# scheme.net
KiCad netlist of a schematic drawn in EAGLE
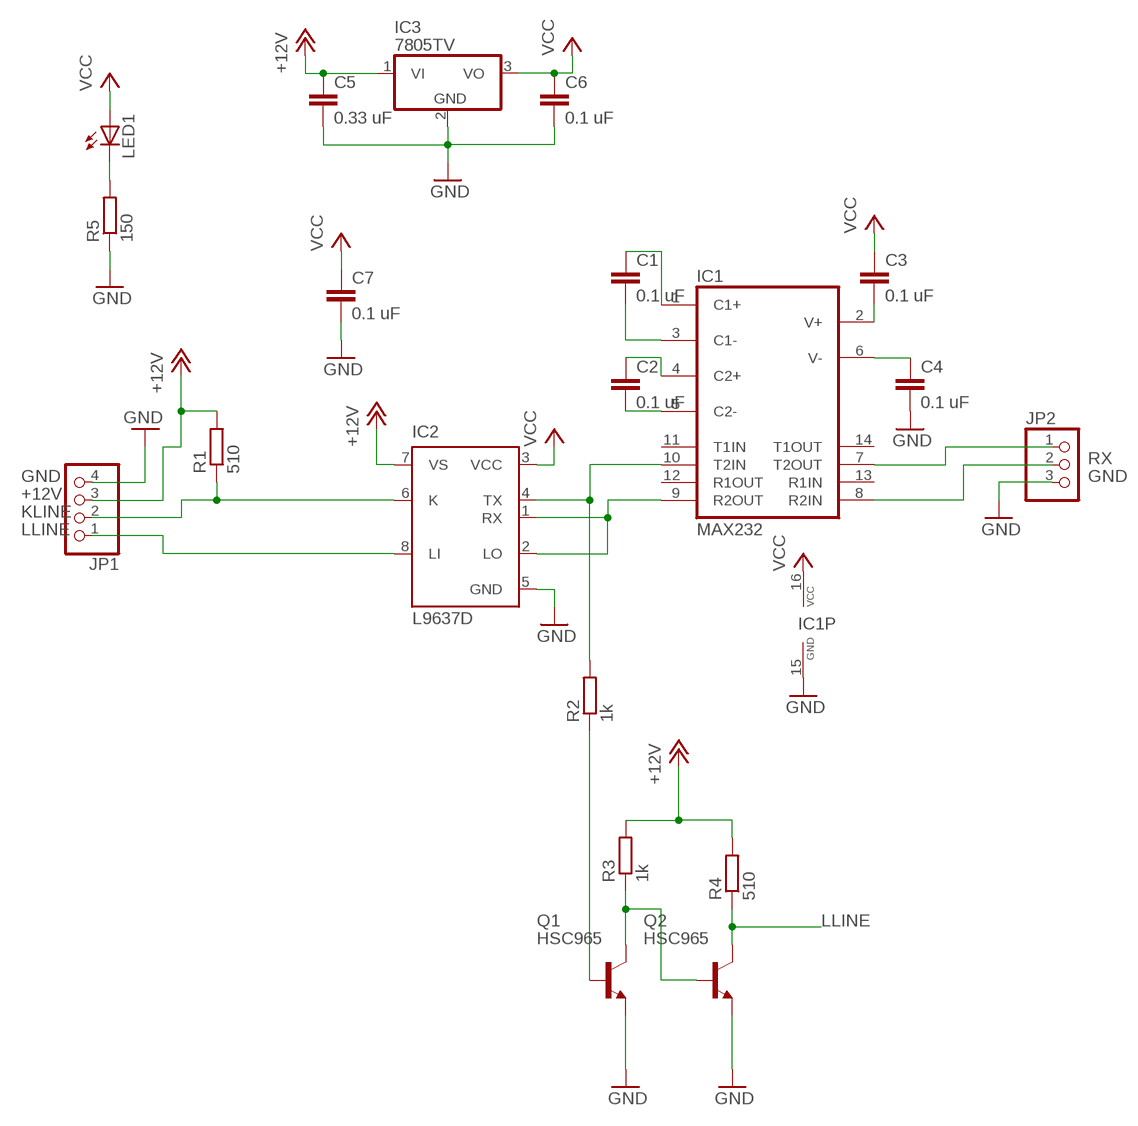
[diagram p0: schematic, sheet 1]

(export (version "E")
  (design (tool "Eeschema 10.0.6"))
  (components
    (comp (ref "C1")
      (value "0.1 uF")
      (footprint "eagle-import:C0805K")
      (libsource (lib "eagle-import") (part "C-EUC0805K"))
    )
    (comp (ref "C2")
      (value "0.1 uF")
      (footprint "eagle-import:C0805K")
      (libsource (lib "eagle-import") (part "C-EUC0805K"))
    )
    (comp (ref "C3")
      (value "0.1 uF")
      (footprint "eagle-import:C0805K")
      (libsource (lib "eagle-import") (part "C-EUC0805K"))
    )
    (comp (ref "C4")
      (value "0.1 uF")
      (footprint "eagle-import:C0805K")
      (libsource (lib "eagle-import") (part "C-EUC0805K"))
    )
    (comp (ref "C5")
      (value "0.33 uF")
      (footprint "eagle-import:C0805K")
      (libsource (lib "eagle-import") (part "C-EUC0805K"))
    )
    (comp (ref "C6")
      (value "0.1 uF")
      (footprint "eagle-import:C0805K")
      (libsource (lib "eagle-import") (part "C-EUC0805K"))
    )
    (comp (ref "C7")
      (value "0.1 uF")
      (footprint "eagle-import:C0805K")
      (libsource (lib "eagle-import") (part "C-EUC0805K"))
    )
    (comp (ref "IC1")
      (value "MAX232")
      (footprint "eagle-import:DIL16")
      (fields (field (name "MF") "MAXIM") (field (name "MPN") "MAX232ACPE+"))
      (libsource (lib "eagle-import") (part "MAX232"))
    )
    (comp (ref "IC2")
      (value "L9637D")
      (footprint "eagle-import:SO08")
      (libsource (lib "eagle-import") (part "L9637D"))
    )
    (comp (ref "IC3")
      (value "7805TV")
      (footprint "eagle-import:TO220V")
      (libsource (lib "eagle-import") (part "78TV05"))
    )
    (comp (ref "JP1")
      (value "PINHD-1X4")
      (footprint "eagle-import:1X04")
      (libsource (lib "eagle-import") (part "PINHD-1X4"))
    )
    (comp (ref "JP2")
      (value "PINHD-1X3")
      (footprint "eagle-import:1X03")
      (libsource (lib "eagle-import") (part "PINHD-1X3"))
    )
    (comp (ref "LED1")
      (value "LED3MM")
      (footprint "eagle-import:LED3MM")
      (libsource (lib "eagle-import") (part "LED3MM"))
    )
    (comp (ref "Q1")
      (value "HSC965")
      (footprint "eagle-import:TO92-")
      (libsource (lib "eagle-import") (part "HSC965"))
    )
    (comp (ref "Q2")
      (value "HSC965")
      (footprint "eagle-import:TO92-")
      (libsource (lib "eagle-import") (part "HSC965"))
    )
    (comp (ref "R1")
      (value "510")
      (footprint "eagle-import:R0805")
      (libsource (lib "eagle-import") (part "R-EU_R0805"))
    )
    (comp (ref "R2")
      (value "1k")
      (footprint "eagle-import:R0805")
      (libsource (lib "eagle-import") (part "R-EU_R0805"))
    )
    (comp (ref "R3")
      (value "1k")
      (footprint "eagle-import:R0805")
      (libsource (lib "eagle-import") (part "R-EU_R0805"))
    )
    (comp (ref "R4")
      (value "510")
      (footprint "eagle-import:R0805")
      (libsource (lib "eagle-import") (part "R-EU_R0805"))
    )
    (comp (ref "R5")
      (value "150")
      (footprint "eagle-import:R0805")
      (libsource (lib "eagle-import") (part "R-EU_R0805"))
    )
  )
  (nets
    (net (code "1") (name "+12V") (class "Default")
      (node (ref "C5") (pin "1") (pinfunction "1_1") (pintype "passive"))
      (node (ref "IC2") (pin "7") (pinfunction "VS_7") (pintype "power_in"))
      (node (ref "IC3") (pin "1") (pinfunction "VI_1") (pintype "input"))
      (node (ref "JP1") (pin "3") (pinfunction "3_3") (pintype "passive"))
      (node (ref "R1") (pin "2") (pinfunction "2_2") (pintype "passive"))
      (node (ref "R3") (pin "2") (pinfunction "2_2") (pintype "passive"))
      (node (ref "R4") (pin "2") (pinfunction "2_2") (pintype "passive"))
    )
    (net (code "2") (name "/KLINE") (class "Default")
      (node (ref "IC2") (pin "6") (pinfunction "K_6") (pintype "input"))
      (node (ref "JP1") (pin "2") (pinfunction "2_2") (pintype "passive"))
      (node (ref "R1") (pin "1") (pinfunction "1_1") (pintype "passive"))
    )
    (net (code "3") (name "/LLINE") (class "Default")
      (node (ref "IC2") (pin "8") (pinfunction "LI_8") (pintype "input"))
      (node (ref "JP1") (pin "1") (pinfunction "1_1") (pintype "passive"))
      (node (ref "Q2") (pin "2") (pinfunction "C_2") (pintype "passive"))
      (node (ref "R4") (pin "1") (pinfunction "1_1") (pintype "passive"))
    )
    (net (code "4") (name "/RX") (class "Default")
      (node (ref "IC1") (pin "8") (pinfunction "R2IN_8") (pintype "input"))
      (node (ref "JP2") (pin "2") (pinfunction "2_2") (pintype "passive"))
    )
    (net (code "5") (name "GND") (class "Default")
      (node (ref "C4") (pin "2") (pinfunction "2_2") (pintype "passive"))
      (node (ref "C5") (pin "2") (pinfunction "2_2") (pintype "passive"))
      (node (ref "C6") (pin "2") (pinfunction "2_2") (pintype "passive"))
      (node (ref "C7") (pin "2") (pinfunction "2_2") (pintype "passive"))
      (node (ref "IC1") (pin "15") (pinfunction "GND_15") (pintype "power_in"))
      (node (ref "IC2") (pin "5") (pinfunction "GND_5") (pintype "power_in"))
      (node (ref "IC3") (pin "2") (pinfunction "GND_2") (pintype "passive"))
      (node (ref "JP1") (pin "4") (pinfunction "4_4") (pintype "passive"))
      (node (ref "JP2") (pin "3") (pinfunction "3_3") (pintype "passive"))
      (node (ref "Q1") (pin "3") (pinfunction "E_3") (pintype "passive"))
      (node (ref "Q2") (pin "3") (pinfunction "E_3") (pintype "passive"))
      (node (ref "R5") (pin "1") (pinfunction "1_1") (pintype "passive"))
    )
    (net (code "6") (name "Net-(IC1A-C1+)") (class "Default")
      (node (ref "C1") (pin "1") (pinfunction "1_1") (pintype "passive"))
      (node (ref "IC1") (pin "1") (pinfunction "C1+_1") (pintype "bidirectional"))
    )
    (net (code "7") (name "Net-(IC1A-C1-)") (class "Default")
      (node (ref "C1") (pin "2") (pinfunction "2_2") (pintype "passive"))
      (node (ref "IC1") (pin "3") (pinfunction "C1-_3") (pintype "bidirectional"))
    )
    (net (code "8") (name "Net-(IC1A-C2+)") (class "Default")
      (node (ref "C2") (pin "1") (pinfunction "1_1") (pintype "passive"))
      (node (ref "IC1") (pin "4") (pinfunction "C2+_4") (pintype "bidirectional"))
    )
    (net (code "9") (name "Net-(IC1A-C2-)") (class "Default")
      (node (ref "C2") (pin "2") (pinfunction "2_2") (pintype "passive"))
      (node (ref "IC1") (pin "5") (pinfunction "C2-_5") (pintype "bidirectional"))
    )
    (net (code "10") (name "Net-(IC1A-R2OUT)") (class "Default")
      (node (ref "IC1") (pin "9") (pinfunction "R2OUT_9") (pintype "output"))
      (node (ref "IC2") (pin "1") (pinfunction "RX_1") (pintype "output"))
      (node (ref "IC2") (pin "2") (pinfunction "LO_2") (pintype "output"))
    )
    (net (code "11") (name "Net-(IC1A-T2IN)") (class "Default")
      (node (ref "IC1") (pin "10") (pinfunction "T2IN_10") (pintype "input"))
      (node (ref "IC2") (pin "4") (pinfunction "TX_4") (pintype "input"))
      (node (ref "R2") (pin "2") (pinfunction "2_2") (pintype "passive"))
    )
    (net (code "12") (name "Net-(IC1A-T2OUT)") (class "Default")
      (node (ref "IC1") (pin "7") (pinfunction "T2OUT_7") (pintype "output"))
      (node (ref "JP2") (pin "1") (pinfunction "1_1") (pintype "passive"))
    )
    (net (code "13") (name "Net-(IC1A-V+)") (class "Default")
      (node (ref "C3") (pin "2") (pinfunction "2_2") (pintype "passive"))
      (node (ref "IC1") (pin "2") (pinfunction "V+_2") (pintype "bidirectional"))
    )
    (net (code "14") (name "Net-(IC1A-V-)") (class "Default")
      (node (ref "C4") (pin "1") (pinfunction "1_1") (pintype "passive"))
      (node (ref "IC1") (pin "6") (pinfunction "V-_6") (pintype "bidirectional"))
    )
    (net (code "15") (name "Net-(LED1-C)") (class "Default")
      (node (ref "LED1") (pin "K") (pinfunction "C_K") (pintype "passive"))
      (node (ref "R5") (pin "2") (pinfunction "2_2") (pintype "passive"))
    )
    (net (code "16") (name "Net-(Q1-B)") (class "Default")
      (node (ref "Q1") (pin "1") (pinfunction "B_1") (pintype "passive"))
      (node (ref "R2") (pin "1") (pinfunction "1_1") (pintype "passive"))
    )
    (net (code "17") (name "Net-(Q1-C)") (class "Default")
      (node (ref "Q1") (pin "2") (pinfunction "C_2") (pintype "passive"))
      (node (ref "Q2") (pin "1") (pinfunction "B_1") (pintype "passive"))
      (node (ref "R3") (pin "1") (pinfunction "1_1") (pintype "passive"))
    )
    (net (code "18") (name "VCC") (class "Default")
      (node (ref "C3") (pin "1") (pinfunction "1_1") (pintype "passive"))
      (node (ref "C6") (pin "1") (pinfunction "1_1") (pintype "passive"))
      (node (ref "C7") (pin "1") (pinfunction "1_1") (pintype "passive"))
      (node (ref "IC1") (pin "16") (pinfunction "VCC_16") (pintype "power_in"))
      (node (ref "IC2") (pin "3") (pinfunction "VCC_3") (pintype "power_in"))
      (node (ref "IC3") (pin "3") (pinfunction "VO_3") (pintype "passive"))
      (node (ref "LED1") (pin "A") (pinfunction "A_A") (pintype "passive"))
    )
    (net (code "19") (name "unconnected-(IC1A-R1IN-Pad13)") (class "Default")
      (node (ref "IC1") (pin "13") (pinfunction "R1IN_13") (pintype "input"))
    )
    (net (code "20") (name "unconnected-(IC1A-R1OUT-Pad12)") (class "Default")
      (node (ref "IC1") (pin "12") (pinfunction "R1OUT_12") (pintype "output"))
    )
    (net (code "21") (name "unconnected-(IC1A-T1IN-Pad11)") (class "Default")
      (node (ref "IC1") (pin "11") (pinfunction "T1IN_11") (pintype "input"))
    )
    (net (code "22") (name "unconnected-(IC1A-T1OUT-Pad14)") (class "Default")
      (node (ref "IC1") (pin "14") (pinfunction "T1OUT_14") (pintype "output"))
    )
  )
)
